# P4VGA565.net
KiCad netlist of a schematic drawn in EasyEDA Pro
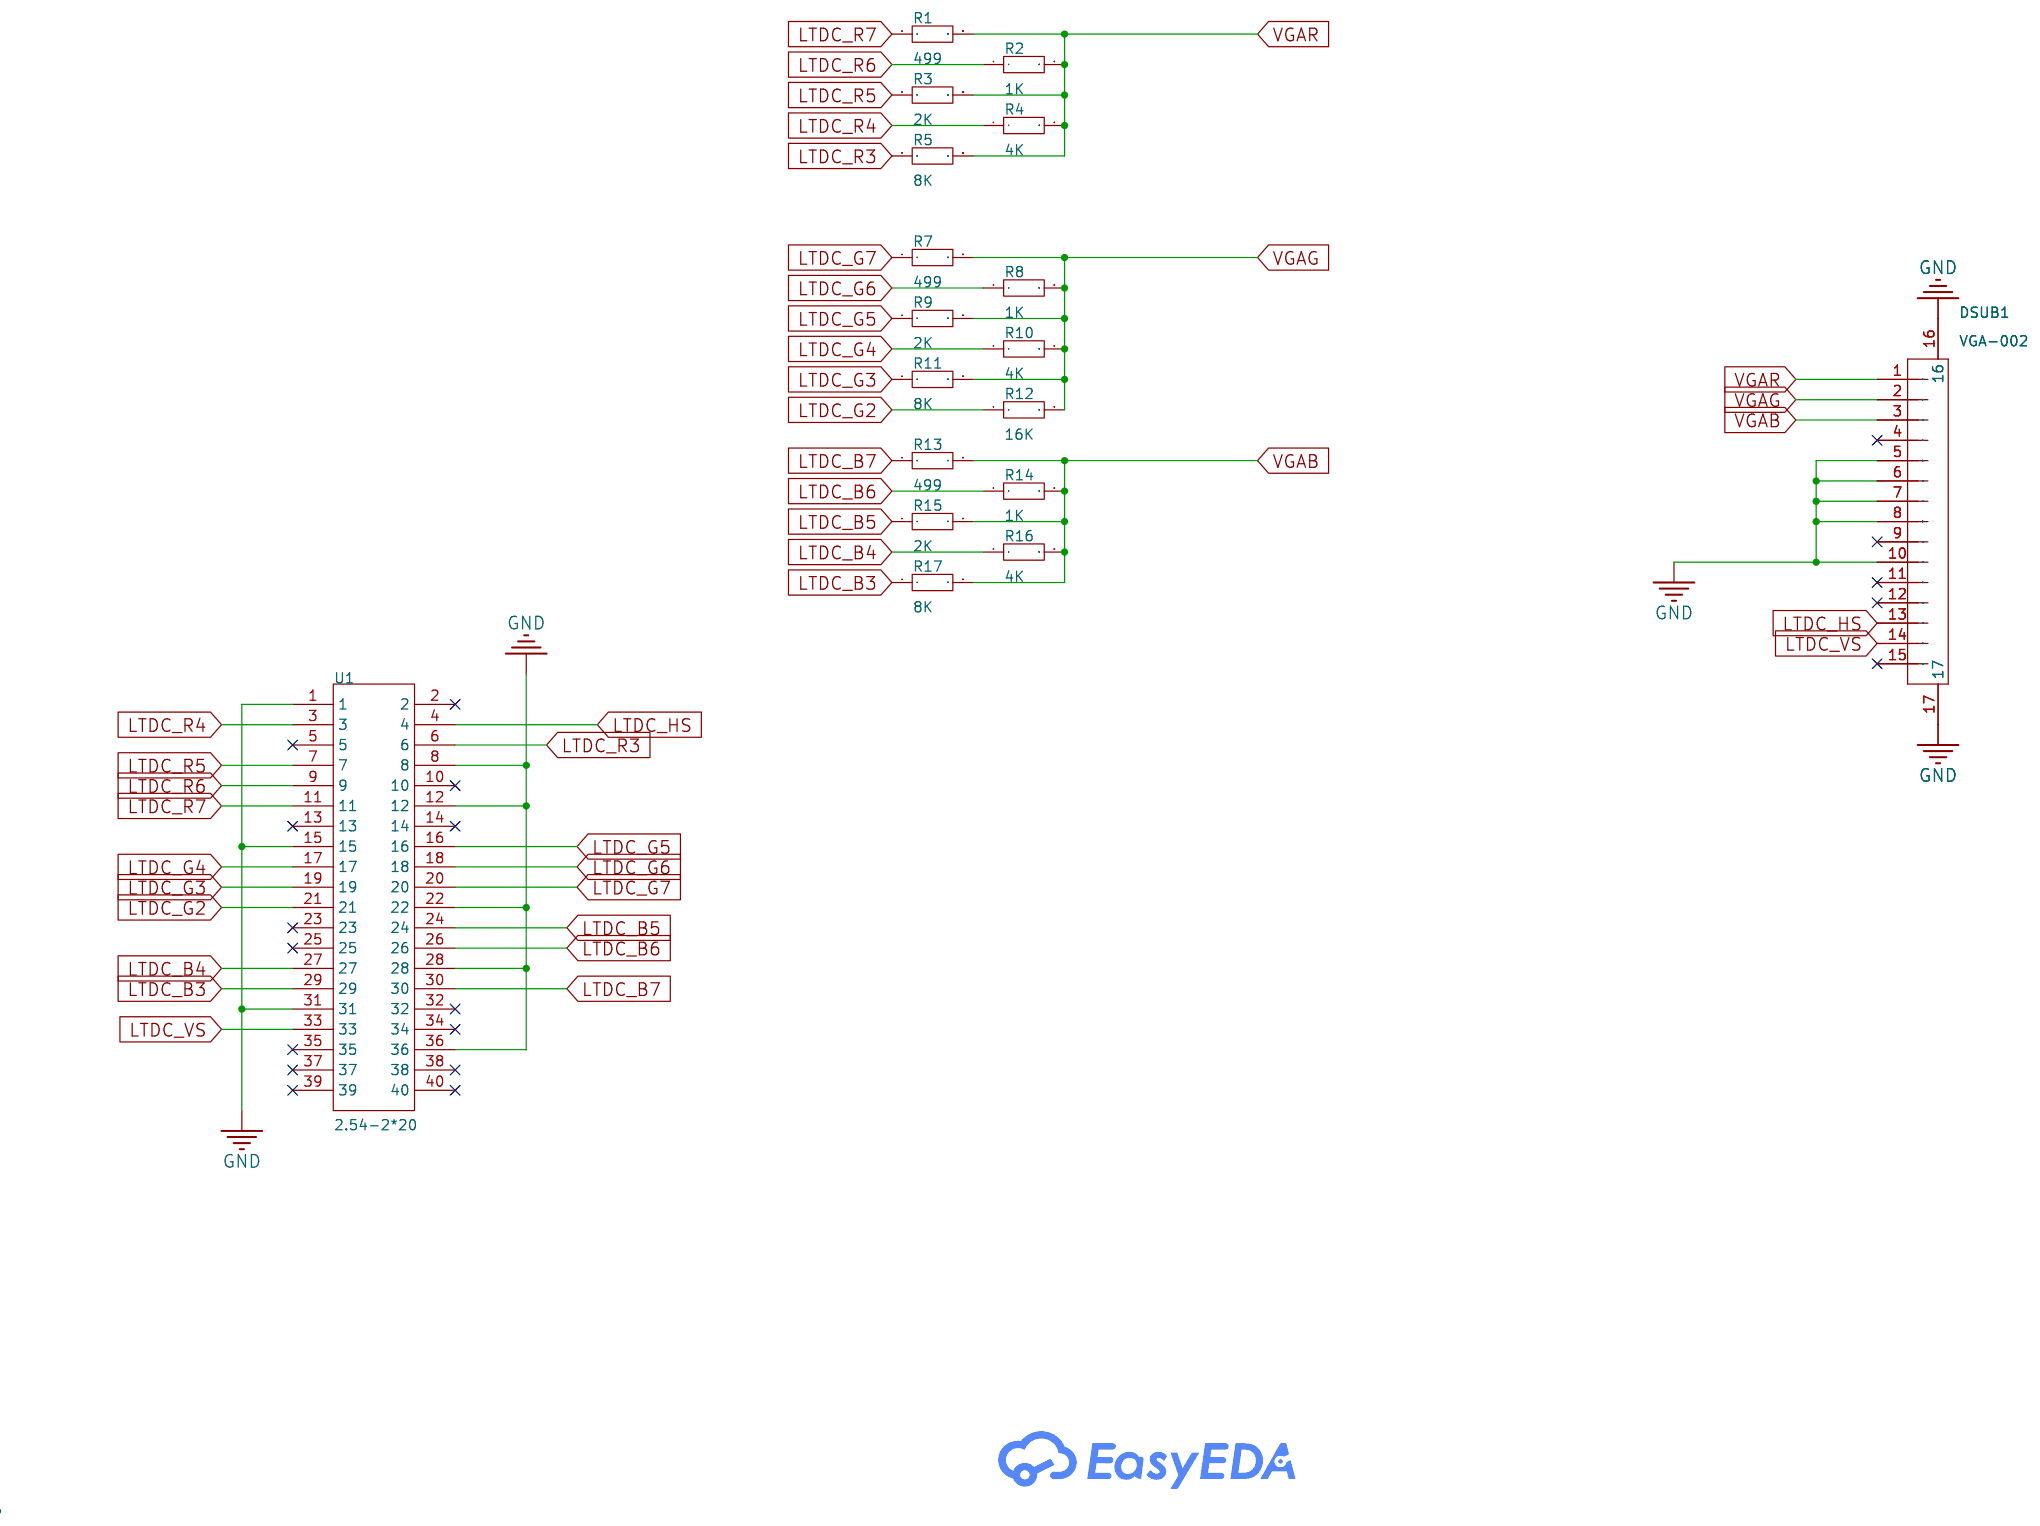
[diagram p0: schematic sheet]

(export (version "E")
  (design (tool "Eeschema 10.0.6"))
  (components
    (comp (ref "DSUB1")
      (value "VGA-002")
      (footprint "easyedapro:D-SUB-TH_VGA-002")
      (fields (field (name "Manufacturer") "BOOMELE(博穆精密)"))
      (libsource (lib "easyedapro") (part "VGA-002"))
    )
    (comp (ref "R1") (value "499") (footprint "easyedapro:R0603") (libsource (lib "easyedapro") (part "Res")))
    (comp (ref "R2") (value "1K") (footprint "easyedapro:R0603") (libsource (lib "easyedapro") (part "Res")))
    (comp (ref "R3") (value "2K") (footprint "easyedapro:R0603") (libsource (lib "easyedapro") (part "Res")))
    (comp (ref "R4") (value "4K") (footprint "easyedapro:R0603") (libsource (lib "easyedapro") (part "Res")))
    (comp (ref "R5") (value "8K") (footprint "easyedapro:R0603") (libsource (lib "easyedapro") (part "Res")))
    (comp (ref "R7") (value "499") (footprint "easyedapro:R0603") (libsource (lib "easyedapro") (part "Res")))
    (comp (ref "R8") (value "1K") (footprint "easyedapro:R0603") (libsource (lib "easyedapro") (part "Res")))
    (comp (ref "R9") (value "2K") (footprint "easyedapro:R0603") (libsource (lib "easyedapro") (part "Res")))
    (comp (ref "R10") (value "4K") (footprint "easyedapro:R0603") (libsource (lib "easyedapro") (part "Res")))
    (comp (ref "R11") (value "8K") (footprint "easyedapro:R0603") (libsource (lib "easyedapro") (part "Res")))
    (comp (ref "R12")
      (value "16K")
      (footprint "easyedapro:R0603")
      (libsource (lib "easyedapro") (part "Res"))
    )
    (comp (ref "R13")
      (value "499")
      (footprint "easyedapro:R0603")
      (libsource (lib "easyedapro") (part "Res"))
    )
    (comp (ref "R14") (value "1K") (footprint "easyedapro:R0603") (libsource (lib "easyedapro") (part "Res")))
    (comp (ref "R15") (value "2K") (footprint "easyedapro:R0603") (libsource (lib "easyedapro") (part "Res")))
    (comp (ref "R16") (value "4K") (footprint "easyedapro:R0603") (libsource (lib "easyedapro") (part "Res")))
    (comp (ref "R17") (value "8K") (footprint "easyedapro:R0603") (libsource (lib "easyedapro") (part "Res")))
    (comp (ref "U1")
      (value "2.54-2*20")
      (footprint "easyedapro:HDR-TH_40P-P2.54-V-F-R2-C20-S2.54")
      (fields (field (name "Manufacturer") "ZHOURI(洲日)"))
      (libsource (lib "easyedapro") (part "2.54-2*20"))
    )
  )
  (nets
    (net (code "1") (name "GND") (class "Default")
      (node (ref "DSUB1") (pin "10") (pinfunction "10_10") (pintype "unspecified"))
      (node (ref "DSUB1") (pin "16") (pinfunction "16_16") (pintype "unspecified"))
      (node (ref "DSUB1") (pin "17") (pinfunction "17_17") (pintype "unspecified"))
      (node (ref "DSUB1") (pin "5") (pinfunction "5_5") (pintype "unspecified"))
      (node (ref "DSUB1") (pin "6") (pinfunction "6_6") (pintype "unspecified"))
      (node (ref "DSUB1") (pin "7") (pinfunction "7_7") (pintype "unspecified"))
      (node (ref "DSUB1") (pin "8") (pinfunction "8_8") (pintype "unspecified"))
      (node (ref "U1") (pin "1") (pinfunction "1_1") (pintype "unspecified"))
      (node (ref "U1") (pin "12") (pinfunction "12_12") (pintype "unspecified"))
      (node (ref "U1") (pin "15") (pinfunction "15_15") (pintype "unspecified"))
      (node (ref "U1") (pin "22") (pinfunction "22_22") (pintype "unspecified"))
      (node (ref "U1") (pin "28") (pinfunction "28_28") (pintype "unspecified"))
      (node (ref "U1") (pin "31") (pinfunction "31_31") (pintype "unspecified"))
      (node (ref "U1") (pin "36") (pinfunction "36_36") (pintype "unspecified"))
      (node (ref "U1") (pin "8") (pinfunction "8_8") (pintype "unspecified"))
    )
    (net (code "2") (name "LTDC_B3") (class "Default")
      (node (ref "R17") (pin "1") (pinfunction "1_1") (pintype "input"))
      (node (ref "U1") (pin "29") (pinfunction "29_29") (pintype "unspecified"))
    )
    (net (code "3") (name "LTDC_B4") (class "Default")
      (node (ref "R16") (pin "1") (pinfunction "1_1") (pintype "input"))
      (node (ref "U1") (pin "27") (pinfunction "27_27") (pintype "unspecified"))
    )
    (net (code "4") (name "LTDC_B5") (class "Default")
      (node (ref "R15") (pin "1") (pinfunction "1_1") (pintype "input"))
      (node (ref "U1") (pin "24") (pinfunction "24_24") (pintype "unspecified"))
    )
    (net (code "5") (name "LTDC_B6") (class "Default")
      (node (ref "R14") (pin "1") (pinfunction "1_1") (pintype "input"))
      (node (ref "U1") (pin "26") (pinfunction "26_26") (pintype "unspecified"))
    )
    (net (code "6") (name "LTDC_B7") (class "Default")
      (node (ref "R13") (pin "1") (pinfunction "1_1") (pintype "input"))
      (node (ref "U1") (pin "30") (pinfunction "30_30") (pintype "unspecified"))
    )
    (net (code "7") (name "LTDC_G2") (class "Default")
      (node (ref "R12") (pin "1") (pinfunction "1_1") (pintype "input"))
      (node (ref "U1") (pin "21") (pinfunction "21_21") (pintype "unspecified"))
    )
    (net (code "8") (name "LTDC_G3") (class "Default")
      (node (ref "R11") (pin "1") (pinfunction "1_1") (pintype "input"))
      (node (ref "U1") (pin "19") (pinfunction "19_19") (pintype "unspecified"))
    )
    (net (code "9") (name "LTDC_G4") (class "Default")
      (node (ref "R10") (pin "1") (pinfunction "1_1") (pintype "input"))
      (node (ref "U1") (pin "17") (pinfunction "17_17") (pintype "unspecified"))
    )
    (net (code "10") (name "LTDC_G5") (class "Default")
      (node (ref "R9") (pin "1") (pinfunction "1_1") (pintype "input"))
      (node (ref "U1") (pin "16") (pinfunction "16_16") (pintype "unspecified"))
    )
    (net (code "11") (name "LTDC_G6") (class "Default")
      (node (ref "R8") (pin "1") (pinfunction "1_1") (pintype "input"))
      (node (ref "U1") (pin "18") (pinfunction "18_18") (pintype "unspecified"))
    )
    (net (code "12") (name "LTDC_G7") (class "Default")
      (node (ref "R7") (pin "1") (pinfunction "1_1") (pintype "input"))
      (node (ref "U1") (pin "20") (pinfunction "20_20") (pintype "unspecified"))
    )
    (net (code "13") (name "LTDC_HS") (class "Default")
      (node (ref "DSUB1") (pin "13") (pinfunction "13_13") (pintype "unspecified"))
      (node (ref "U1") (pin "4") (pinfunction "4_4") (pintype "unspecified"))
    )
    (net (code "14") (name "LTDC_R3") (class "Default")
      (node (ref "R5") (pin "1") (pinfunction "1_1") (pintype "input"))
      (node (ref "U1") (pin "6") (pinfunction "6_6") (pintype "unspecified"))
    )
    (net (code "15") (name "LTDC_R4") (class "Default")
      (node (ref "R4") (pin "1") (pinfunction "1_1") (pintype "input"))
      (node (ref "U1") (pin "3") (pinfunction "3_3") (pintype "unspecified"))
    )
    (net (code "16") (name "LTDC_R5") (class "Default")
      (node (ref "R3") (pin "1") (pinfunction "1_1") (pintype "input"))
      (node (ref "U1") (pin "7") (pinfunction "7_7") (pintype "unspecified"))
    )
    (net (code "17") (name "LTDC_R6") (class "Default")
      (node (ref "R2") (pin "1") (pinfunction "1_1") (pintype "input"))
      (node (ref "U1") (pin "9") (pinfunction "9_9") (pintype "unspecified"))
    )
    (net (code "18") (name "LTDC_R7") (class "Default")
      (node (ref "R1") (pin "1") (pinfunction "1_1") (pintype "input"))
      (node (ref "U1") (pin "11") (pinfunction "11_11") (pintype "unspecified"))
    )
    (net (code "19") (name "LTDC_VS") (class "Default")
      (node (ref "DSUB1") (pin "14") (pinfunction "14_14") (pintype "unspecified"))
      (node (ref "U1") (pin "33") (pinfunction "33_33") (pintype "unspecified"))
    )
    (net (code "20") (name "VGAB") (class "Default")
      (node (ref "DSUB1") (pin "3") (pinfunction "3_3") (pintype "unspecified"))
      (node (ref "R13") (pin "2") (pinfunction "2_2") (pintype "input"))
      (node (ref "R14") (pin "2") (pinfunction "2_2") (pintype "input"))
      (node (ref "R15") (pin "2") (pinfunction "2_2") (pintype "input"))
      (node (ref "R16") (pin "2") (pinfunction "2_2") (pintype "input"))
      (node (ref "R17") (pin "2") (pinfunction "2_2") (pintype "input"))
    )
    (net (code "21") (name "VGAG") (class "Default")
      (node (ref "DSUB1") (pin "2") (pinfunction "2_2") (pintype "unspecified"))
      (node (ref "R10") (pin "2") (pinfunction "2_2") (pintype "input"))
      (node (ref "R11") (pin "2") (pinfunction "2_2") (pintype "input"))
      (node (ref "R12") (pin "2") (pinfunction "2_2") (pintype "input"))
      (node (ref "R7") (pin "2") (pinfunction "2_2") (pintype "input"))
      (node (ref "R8") (pin "2") (pinfunction "2_2") (pintype "input"))
      (node (ref "R9") (pin "2") (pinfunction "2_2") (pintype "input"))
    )
    (net (code "22") (name "VGAR") (class "Default")
      (node (ref "DSUB1") (pin "1") (pinfunction "1_1") (pintype "unspecified"))
      (node (ref "R1") (pin "2") (pinfunction "2_2") (pintype "input"))
      (node (ref "R2") (pin "2") (pinfunction "2_2") (pintype "input"))
      (node (ref "R3") (pin "2") (pinfunction "2_2") (pintype "input"))
      (node (ref "R4") (pin "2") (pinfunction "2_2") (pintype "input"))
      (node (ref "R5") (pin "2") (pinfunction "2_2") (pintype "input"))
    )
    (net (code "23") (name "unconnected-(DSUB1-Pad4)") (class "Default")
      (node (ref "DSUB1") (pin "4") (pinfunction "4_4") (pintype "unspecified+no_connect"))
    )
    (net (code "24") (name "unconnected-(DSUB1-Pad9)") (class "Default")
      (node (ref "DSUB1") (pin "9") (pinfunction "9_9") (pintype "unspecified+no_connect"))
    )
    (net (code "25") (name "unconnected-(DSUB1-Pad11)") (class "Default")
      (node (ref "DSUB1") (pin "11") (pinfunction "11_11") (pintype "unspecified+no_connect"))
    )
    (net (code "26") (name "unconnected-(DSUB1-Pad12)") (class "Default")
      (node (ref "DSUB1") (pin "12") (pinfunction "12_12") (pintype "unspecified+no_connect"))
    )
    (net (code "27") (name "unconnected-(DSUB1-Pad15)") (class "Default")
      (node (ref "DSUB1") (pin "15") (pinfunction "15_15") (pintype "unspecified+no_connect"))
    )
    (net (code "28") (name "unconnected-(U1-Pad2)") (class "Default")
      (node (ref "U1") (pin "2") (pinfunction "2_2") (pintype "unspecified+no_connect"))
    )
    (net (code "29") (name "unconnected-(U1-Pad5)") (class "Default")
      (node (ref "U1") (pin "5") (pinfunction "5_5") (pintype "unspecified+no_connect"))
    )
    (net (code "30") (name "unconnected-(U1-Pad10)") (class "Default")
      (node (ref "U1") (pin "10") (pinfunction "10_10") (pintype "unspecified+no_connect"))
    )
    (net (code "31") (name "unconnected-(U1-Pad13)") (class "Default")
      (node (ref "U1") (pin "13") (pinfunction "13_13") (pintype "unspecified+no_connect"))
    )
    (net (code "32") (name "unconnected-(U1-Pad14)") (class "Default")
      (node (ref "U1") (pin "14") (pinfunction "14_14") (pintype "unspecified+no_connect"))
    )
    (net (code "33") (name "unconnected-(U1-Pad23)") (class "Default")
      (node (ref "U1") (pin "23") (pinfunction "23_23") (pintype "unspecified+no_connect"))
    )
    (net (code "34") (name "unconnected-(U1-Pad25)") (class "Default")
      (node (ref "U1") (pin "25") (pinfunction "25_25") (pintype "unspecified+no_connect"))
    )
    (net (code "35") (name "unconnected-(U1-Pad32)") (class "Default")
      (node (ref "U1") (pin "32") (pinfunction "32_32") (pintype "unspecified+no_connect"))
    )
    (net (code "36") (name "unconnected-(U1-Pad34)") (class "Default")
      (node (ref "U1") (pin "34") (pinfunction "34_34") (pintype "unspecified+no_connect"))
    )
    (net (code "37") (name "unconnected-(U1-Pad35)") (class "Default")
      (node (ref "U1") (pin "35") (pinfunction "35_35") (pintype "unspecified+no_connect"))
    )
    (net (code "38") (name "unconnected-(U1-Pad37)") (class "Default")
      (node (ref "U1") (pin "37") (pinfunction "37_37") (pintype "unspecified+no_connect"))
    )
    (net (code "39") (name "unconnected-(U1-Pad38)") (class "Default")
      (node (ref "U1") (pin "38") (pinfunction "38_38") (pintype "unspecified+no_connect"))
    )
    (net (code "40") (name "unconnected-(U1-Pad39)") (class "Default")
      (node (ref "U1") (pin "39") (pinfunction "39_39") (pintype "unspecified+no_connect"))
    )
    (net (code "41") (name "unconnected-(U1-Pad40)") (class "Default")
      (node (ref "U1") (pin "40") (pinfunction "40_40") (pintype "unspecified+no_connect"))
    )
  )
)
